# multi-switches.net
KiCad netlist of a schematic drawn in EAGLE
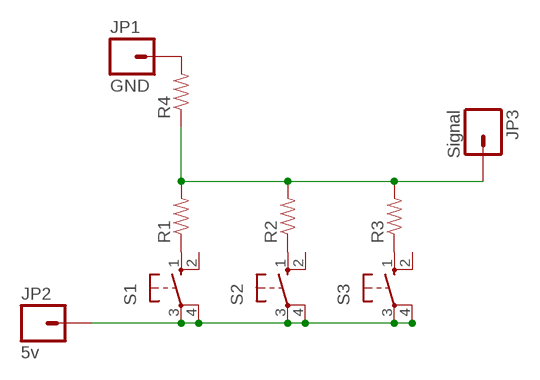
[diagram p0: schematic, sheet 1]

(export (version "E")
  (design (tool "Eeschema 10.0.6"))
  (components
    (comp (ref "JP1")
      (value "GND")
      (footprint "eagle-import:1X01_LONGPAD")
      (libsource (lib "eagle-import") (part "M01PTH_LONGPAD"))
    )
    (comp (ref "JP2")
      (value "5v")
      (footprint "eagle-import:1X01_LONGPAD")
      (libsource (lib "eagle-import") (part "M01PTH_LONGPAD"))
    )
    (comp (ref "JP3")
      (value "Signal")
      (footprint "eagle-import:1X01_LONGPAD")
      (libsource (lib "eagle-import") (part "M01PTH_LONGPAD"))
    )
    (comp (ref "R1")
      (value "RESISTOR1206")
      (footprint "eagle-import:1206")
      (libsource (lib "eagle-import") (part "RESISTOR1206"))
    )
    (comp (ref "R2")
      (value "RESISTOR1206")
      (footprint "eagle-import:1206")
      (libsource (lib "eagle-import") (part "RESISTOR1206"))
    )
    (comp (ref "R3")
      (value "RESISTOR1206")
      (footprint "eagle-import:1206")
      (libsource (lib "eagle-import") (part "RESISTOR1206"))
    )
    (comp (ref "R4")
      (value "RESISTOR1206")
      (footprint "eagle-import:1206")
      (libsource (lib "eagle-import") (part "RESISTOR1206"))
    )
    (comp (ref "S1")
      (value "10-XX")
      (footprint "eagle-import:B3F-10XX")
      (fields (field (name "MPN") "B3F-1000"))
      (libsource (lib "eagle-import") (part "10-XX"))
    )
    (comp (ref "S2")
      (value "10-XX")
      (footprint "eagle-import:B3F-10XX")
      (fields (field (name "MPN") "B3F-1000"))
      (libsource (lib "eagle-import") (part "10-XX"))
    )
    (comp (ref "S3")
      (value "10-XX")
      (footprint "eagle-import:B3F-10XX")
      (fields (field (name "MPN") "B3F-1000"))
      (libsource (lib "eagle-import") (part "10-XX"))
    )
  )
  (nets
    (net (code "1") (name "Net-(JP1-Pad1)") (class "Default")
      (node (ref "JP1") (pin "1") (pinfunction "1_1") (pintype "passive"))
      (node (ref "R4") (pin "2") (pinfunction "2_2") (pintype "passive"))
    )
    (net (code "2") (name "Net-(JP3-Pad1)") (class "Default")
      (node (ref "JP3") (pin "1") (pinfunction "1_1") (pintype "passive"))
      (node (ref "R1") (pin "2") (pinfunction "2_2") (pintype "passive"))
      (node (ref "R2") (pin "2") (pinfunction "2_2") (pintype "passive"))
      (node (ref "R3") (pin "2") (pinfunction "2_2") (pintype "passive"))
      (node (ref "R4") (pin "1") (pinfunction "1_1") (pintype "passive"))
    )
    (net (code "3") (name "Net-(S1-P)") (class "Default")
      (node (ref "JP2") (pin "1") (pinfunction "1_1") (pintype "passive"))
      (node (ref "S1") (pin "3") (pinfunction "P_3") (pintype "passive"))
      (node (ref "S1") (pin "4") (pinfunction "P1_4") (pintype "passive"))
      (node (ref "S2") (pin "3") (pinfunction "P_3") (pintype "passive"))
      (node (ref "S2") (pin "4") (pinfunction "P1_4") (pintype "passive"))
      (node (ref "S3") (pin "3") (pinfunction "P_3") (pintype "passive"))
      (node (ref "S3") (pin "4") (pinfunction "P1_4") (pintype "passive"))
    )
    (net (code "4") (name "Net-(S1-S)") (class "Default")
      (node (ref "R1") (pin "1") (pinfunction "1_1") (pintype "passive"))
      (node (ref "S1") (pin "1") (pinfunction "S_1") (pintype "passive"))
    )
    (net (code "5") (name "Net-(S2-S)") (class "Default")
      (node (ref "R2") (pin "1") (pinfunction "1_1") (pintype "passive"))
      (node (ref "S2") (pin "1") (pinfunction "S_1") (pintype "passive"))
    )
    (net (code "6") (name "Net-(S3-S)") (class "Default")
      (node (ref "R3") (pin "1") (pinfunction "1_1") (pintype "passive"))
      (node (ref "S3") (pin "1") (pinfunction "S_1") (pintype "passive"))
    )
    (net (code "7") (name "unconnected-(S1-S1-Pad2)") (class "Default")
      (node (ref "S1") (pin "2") (pinfunction "S1_2") (pintype "passive"))
    )
    (net (code "8") (name "unconnected-(S2-S1-Pad2)") (class "Default")
      (node (ref "S2") (pin "2") (pinfunction "S1_2") (pintype "passive"))
    )
    (net (code "9") (name "unconnected-(S3-S1-Pad2)") (class "Default")
      (node (ref "S3") (pin "2") (pinfunction "S1_2") (pintype "passive"))
    )
  )
)
